# breakout_Rev0.net
KiCad netlist of a schematic drawn in EAGLE
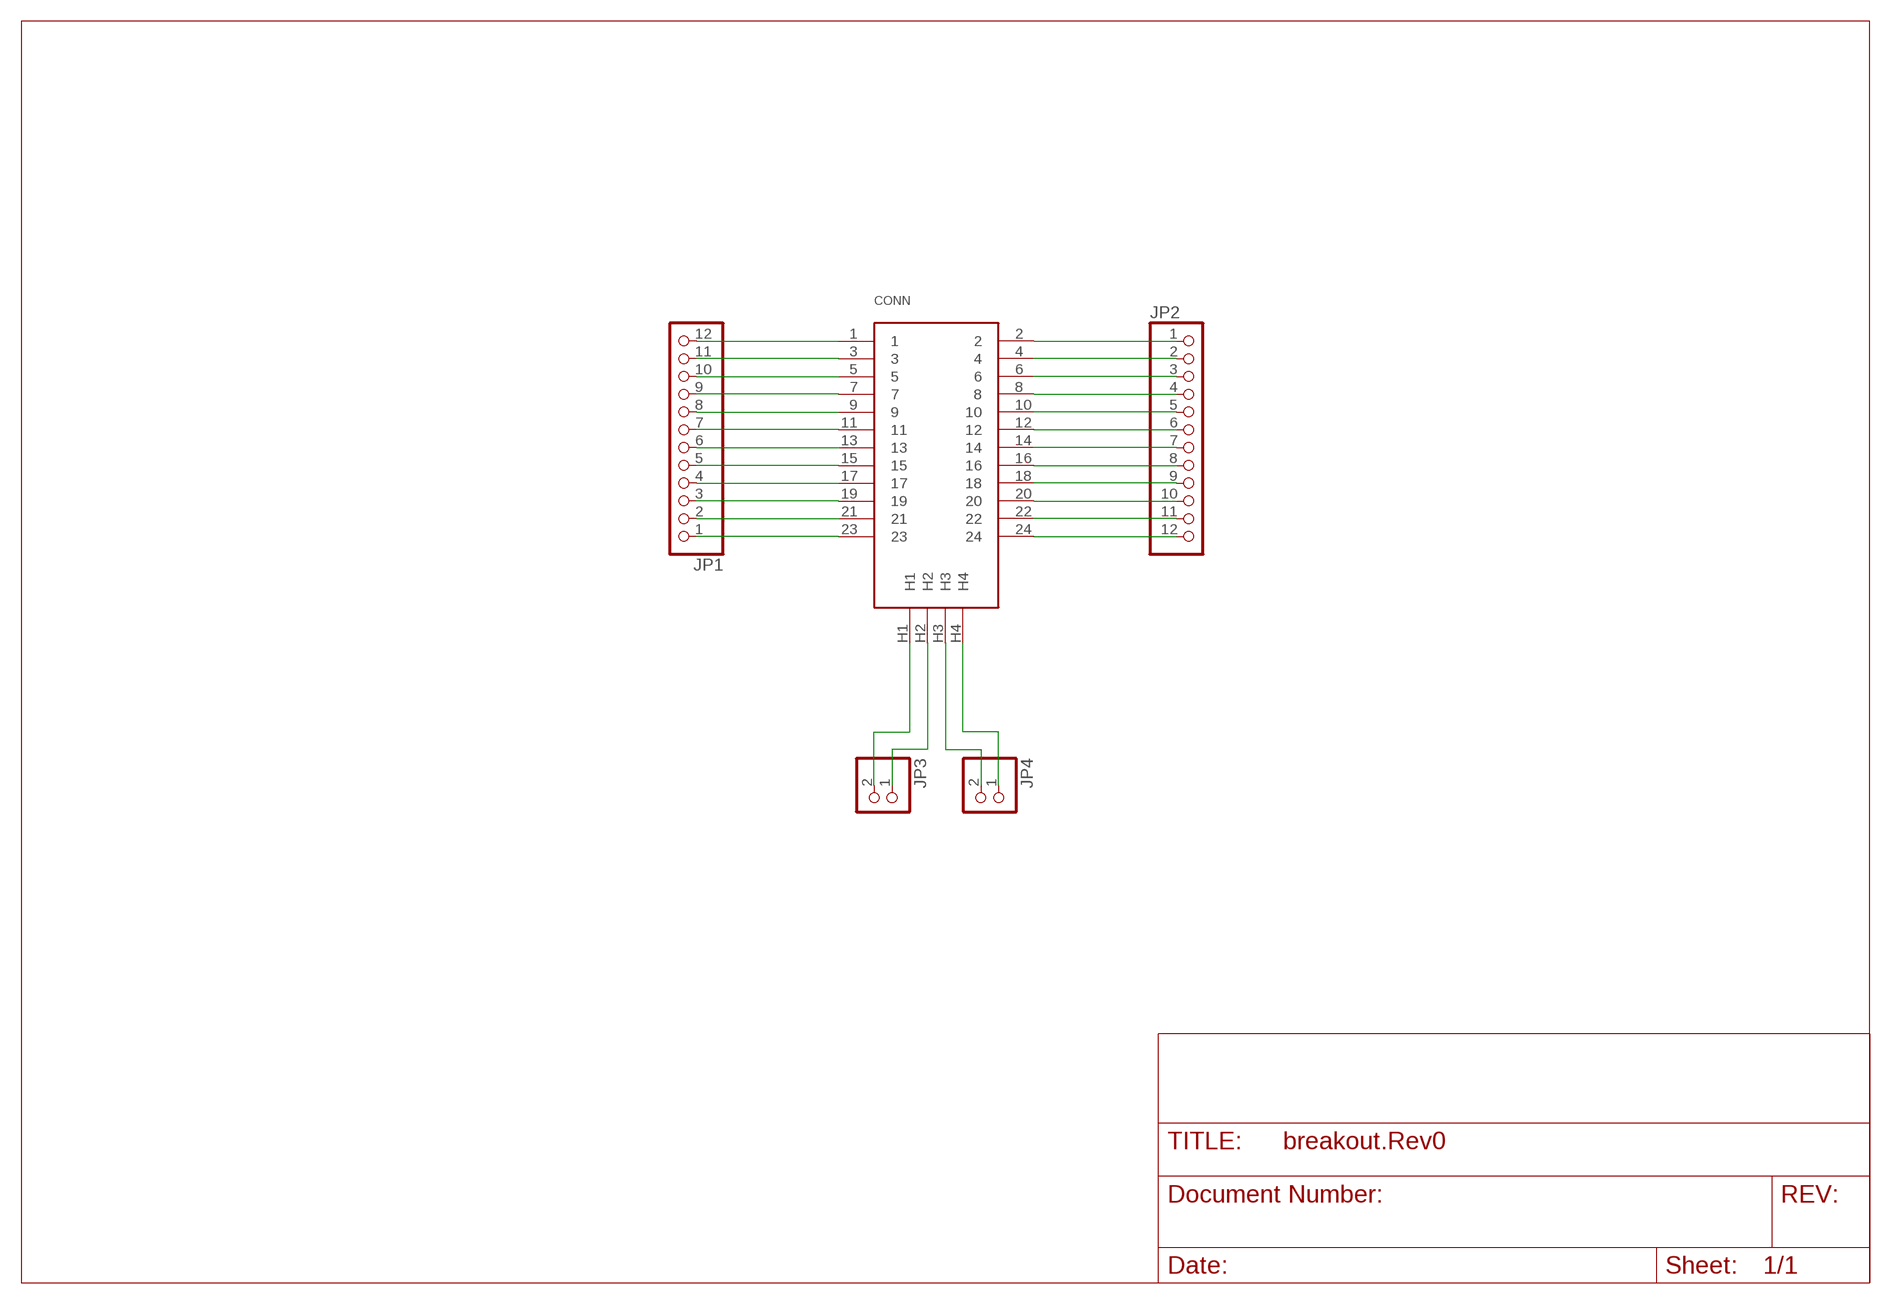
[diagram p0: schematic, sheet 1]

(export (version "E")
  (design (tool "Eeschema 10.0.6"))
  (components
    (comp (ref "CONN")
      (value "BM28B0.6-24DS/2-0.35V(51)")
      (footprint "eagle-import:BM28B0.6-24DS_2-0.35V(51)")
      (libsource (lib "eagle-import") (part "BM28B0.6-24DS/2-0.35V(51)"))
    )
    (comp (ref "JP1")
      (value "PINHD-1X12")
      (footprint "eagle-import:1X12")
      (libsource (lib "eagle-import") (part "PINHD-1X12"))
    )
    (comp (ref "JP2")
      (value "PINHD-1X12")
      (footprint "eagle-import:1X12")
      (libsource (lib "eagle-import") (part "PINHD-1X12"))
    )
    (comp (ref "JP3")
      (value "PINHD-1X2")
      (footprint "eagle-import:1X02")
      (libsource (lib "eagle-import") (part "PINHD-1X2"))
    )
    (comp (ref "JP4")
      (value "PINHD-1X2")
      (footprint "eagle-import:1X02")
      (libsource (lib "eagle-import") (part "PINHD-1X2"))
    )
  )
  (nets
    (net (code "1") (name "Net-(CONN-Pad1)") (class "Default")
      (node (ref "CONN") (pin "1") (pinfunction "1_1") (pintype "bidirectional"))
      (node (ref "JP1") (pin "12") (pinfunction "12_12") (pintype "passive"))
    )
    (net (code "2") (name "Net-(CONN-Pad2)") (class "Default")
      (node (ref "CONN") (pin "2") (pinfunction "2_2") (pintype "bidirectional"))
      (node (ref "JP2") (pin "1") (pinfunction "1_1") (pintype "passive"))
    )
    (net (code "3") (name "Net-(CONN-Pad3)") (class "Default")
      (node (ref "CONN") (pin "3") (pinfunction "3_3") (pintype "bidirectional"))
      (node (ref "JP1") (pin "11") (pinfunction "11_11") (pintype "passive"))
    )
    (net (code "4") (name "Net-(CONN-Pad4)") (class "Default")
      (node (ref "CONN") (pin "4") (pinfunction "4_4") (pintype "bidirectional"))
      (node (ref "JP2") (pin "2") (pinfunction "2_2") (pintype "passive"))
    )
    (net (code "5") (name "Net-(CONN-Pad5)") (class "Default")
      (node (ref "CONN") (pin "5") (pinfunction "5_5") (pintype "bidirectional"))
      (node (ref "JP1") (pin "10") (pinfunction "10_10") (pintype "passive"))
    )
    (net (code "6") (name "Net-(CONN-Pad6)") (class "Default")
      (node (ref "CONN") (pin "6") (pinfunction "6_6") (pintype "bidirectional"))
      (node (ref "JP2") (pin "3") (pinfunction "3_3") (pintype "passive"))
    )
    (net (code "7") (name "Net-(CONN-Pad7)") (class "Default")
      (node (ref "CONN") (pin "7") (pinfunction "7_7") (pintype "bidirectional"))
      (node (ref "JP1") (pin "9") (pinfunction "9_9") (pintype "passive"))
    )
    (net (code "8") (name "Net-(CONN-Pad8)") (class "Default")
      (node (ref "CONN") (pin "8") (pinfunction "8_8") (pintype "bidirectional"))
      (node (ref "JP2") (pin "4") (pinfunction "4_4") (pintype "passive"))
    )
    (net (code "9") (name "Net-(CONN-Pad9)") (class "Default")
      (node (ref "CONN") (pin "9") (pinfunction "9_9") (pintype "bidirectional"))
      (node (ref "JP1") (pin "8") (pinfunction "8_8") (pintype "passive"))
    )
    (net (code "10") (name "Net-(CONN-Pad10)") (class "Default")
      (node (ref "CONN") (pin "10") (pinfunction "10_10") (pintype "bidirectional"))
      (node (ref "JP2") (pin "5") (pinfunction "5_5") (pintype "passive"))
    )
    (net (code "11") (name "Net-(CONN-Pad11)") (class "Default")
      (node (ref "CONN") (pin "11") (pinfunction "11_11") (pintype "bidirectional"))
      (node (ref "JP1") (pin "7") (pinfunction "7_7") (pintype "passive"))
    )
    (net (code "12") (name "Net-(CONN-Pad12)") (class "Default")
      (node (ref "CONN") (pin "12") (pinfunction "12_12") (pintype "bidirectional"))
      (node (ref "JP2") (pin "6") (pinfunction "6_6") (pintype "passive"))
    )
    (net (code "13") (name "Net-(CONN-Pad13)") (class "Default")
      (node (ref "CONN") (pin "13") (pinfunction "13_13") (pintype "bidirectional"))
      (node (ref "JP1") (pin "6") (pinfunction "6_6") (pintype "passive"))
    )
    (net (code "14") (name "Net-(CONN-Pad14)") (class "Default")
      (node (ref "CONN") (pin "14") (pinfunction "14_14") (pintype "bidirectional"))
      (node (ref "JP2") (pin "7") (pinfunction "7_7") (pintype "passive"))
    )
    (net (code "15") (name "Net-(CONN-Pad15)") (class "Default")
      (node (ref "CONN") (pin "15") (pinfunction "15_15") (pintype "bidirectional"))
      (node (ref "JP1") (pin "5") (pinfunction "5_5") (pintype "passive"))
    )
    (net (code "16") (name "Net-(CONN-Pad16)") (class "Default")
      (node (ref "CONN") (pin "16") (pinfunction "16_16") (pintype "bidirectional"))
      (node (ref "JP2") (pin "8") (pinfunction "8_8") (pintype "passive"))
    )
    (net (code "17") (name "Net-(CONN-Pad17)") (class "Default")
      (node (ref "CONN") (pin "17") (pinfunction "17_17") (pintype "bidirectional"))
      (node (ref "JP1") (pin "4") (pinfunction "4_4") (pintype "passive"))
    )
    (net (code "18") (name "Net-(CONN-Pad18)") (class "Default")
      (node (ref "CONN") (pin "18") (pinfunction "18_18") (pintype "bidirectional"))
      (node (ref "JP2") (pin "9") (pinfunction "9_9") (pintype "passive"))
    )
    (net (code "19") (name "Net-(CONN-Pad19)") (class "Default")
      (node (ref "CONN") (pin "19") (pinfunction "19_19") (pintype "bidirectional"))
      (node (ref "JP1") (pin "3") (pinfunction "3_3") (pintype "passive"))
    )
    (net (code "20") (name "Net-(CONN-Pad20)") (class "Default")
      (node (ref "CONN") (pin "20") (pinfunction "20_20") (pintype "bidirectional"))
      (node (ref "JP2") (pin "10") (pinfunction "10_10") (pintype "passive"))
    )
    (net (code "21") (name "Net-(CONN-Pad21)") (class "Default")
      (node (ref "CONN") (pin "21") (pinfunction "21_21") (pintype "bidirectional"))
      (node (ref "JP1") (pin "2") (pinfunction "2_2") (pintype "passive"))
    )
    (net (code "22") (name "Net-(CONN-Pad22)") (class "Default")
      (node (ref "CONN") (pin "22") (pinfunction "22_22") (pintype "bidirectional"))
      (node (ref "JP2") (pin "11") (pinfunction "11_11") (pintype "passive"))
    )
    (net (code "23") (name "Net-(CONN-Pad23)") (class "Default")
      (node (ref "CONN") (pin "23") (pinfunction "23_23") (pintype "bidirectional"))
      (node (ref "JP1") (pin "1") (pinfunction "1_1") (pintype "passive"))
    )
    (net (code "24") (name "Net-(CONN-Pad24)") (class "Default")
      (node (ref "CONN") (pin "24") (pinfunction "24_24") (pintype "bidirectional"))
      (node (ref "JP2") (pin "12") (pinfunction "12_12") (pintype "passive"))
    )
    (net (code "25") (name "Net-(CONN-PadH1)") (class "Default")
      (node (ref "CONN") (pin "H1") (pinfunction "H1_H1") (pintype "bidirectional"))
      (node (ref "JP3") (pin "2") (pinfunction "2_2") (pintype "passive"))
    )
    (net (code "26") (name "Net-(CONN-PadH2)") (class "Default")
      (node (ref "CONN") (pin "H2") (pinfunction "H2_H2") (pintype "bidirectional"))
      (node (ref "JP3") (pin "1") (pinfunction "1_1") (pintype "passive"))
    )
    (net (code "27") (name "Net-(CONN-PadH3)") (class "Default")
      (node (ref "CONN") (pin "H3") (pinfunction "H3_H3") (pintype "bidirectional"))
      (node (ref "JP4") (pin "2") (pinfunction "2_2") (pintype "passive"))
    )
    (net (code "28") (name "Net-(CONN-PadH4)") (class "Default")
      (node (ref "CONN") (pin "H4") (pinfunction "H4_H4") (pintype "bidirectional"))
      (node (ref "JP4") (pin "1") (pinfunction "1_1") (pintype "passive"))
    )
  )
)
